# pc_healthypi_move_bottom_pcb_v3.net
KiCad netlist of a schematic drawn in EAGLE
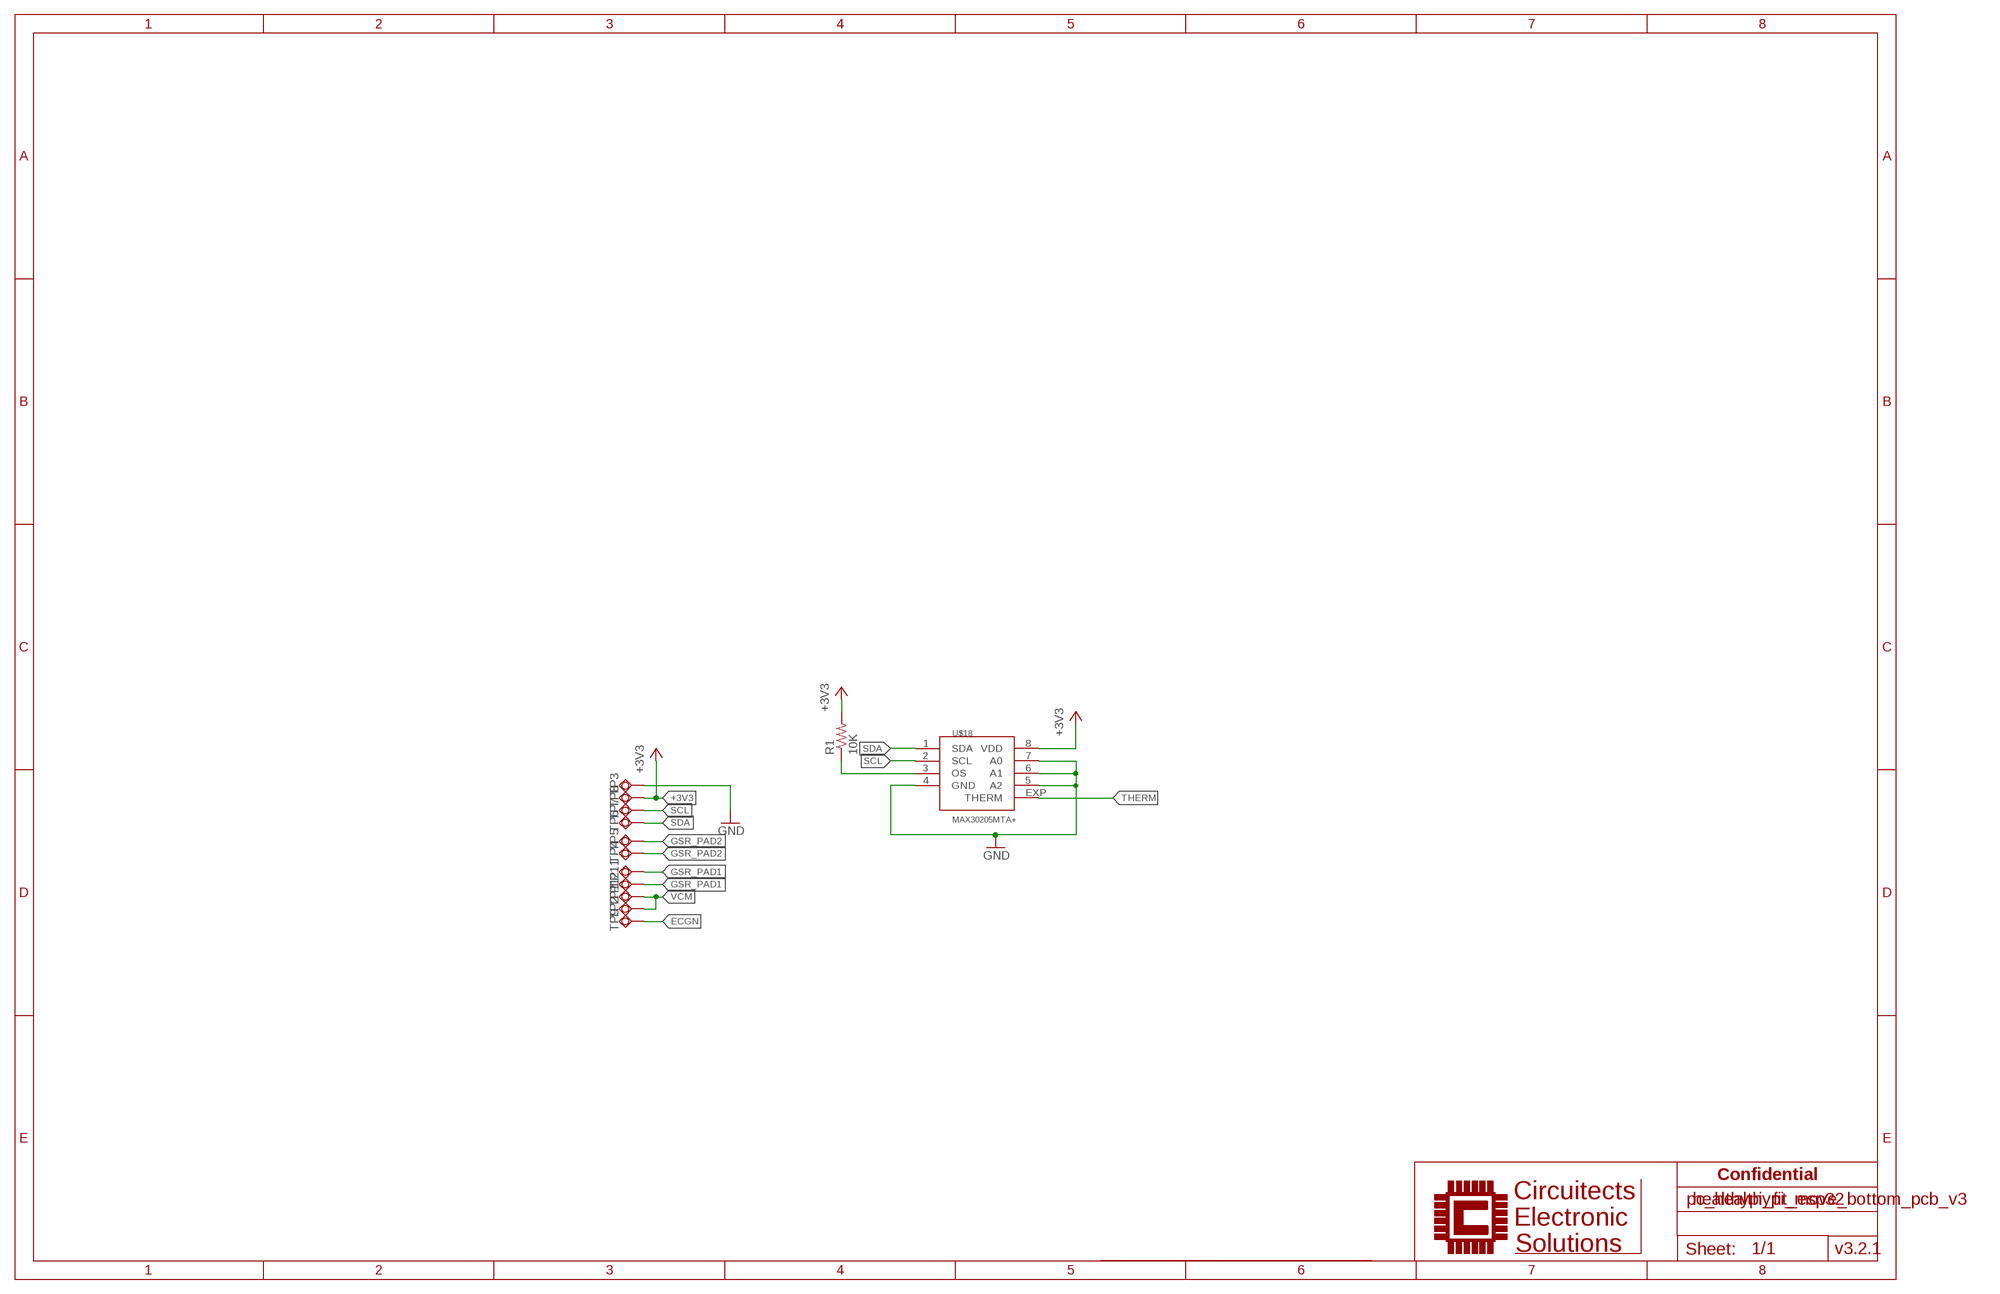
[diagram p0: schematic, sheet 1]

(export (version "E")
  (design (tool "Eeschema 10.0.6"))
  (components
    (comp (ref "R1")
      (value "10K")
      (footprint "eagle-import:R0201")
      (libsource (lib "eagle-import") (part "R-US_R0201"))
    )
    (comp (ref "TP1")
      (value "TPSQTP20SQ")
      (footprint "eagle-import:TP20SQ")
      (libsource (lib "eagle-import") (part "TPSQTP20SQ"))
    )
    (comp (ref "TP2")
      (value "TPSQTP20SQ")
      (footprint "eagle-import:TP20SQ")
      (libsource (lib "eagle-import") (part "TPSQTP20SQ"))
    )
    (comp (ref "TP3")
      (value "TPSQTP20SQ")
      (footprint "eagle-import:TP20SQ")
      (libsource (lib "eagle-import") (part "TPSQTP20SQ"))
    )
    (comp (ref "TP4")
      (value "TPSQTP20SQ")
      (footprint "eagle-import:TP20SQ")
      (libsource (lib "eagle-import") (part "TPSQTP20SQ"))
    )
    (comp (ref "TP5")
      (value "TPSQTP20SQ")
      (footprint "eagle-import:TP20SQ")
      (libsource (lib "eagle-import") (part "TPSQTP20SQ"))
    )
    (comp (ref "TP6")
      (value "TPSQTP20SQ")
      (footprint "eagle-import:TP20SQ")
      (libsource (lib "eagle-import") (part "TPSQTP20SQ"))
    )
    (comp (ref "TP7")
      (value "TPSQTP20SQ")
      (footprint "eagle-import:TP20SQ")
      (libsource (lib "eagle-import") (part "TPSQTP20SQ"))
    )
    (comp (ref "TP8")
      (value "TPSQTP20SQ")
      (footprint "eagle-import:TP20SQ")
      (libsource (lib "eagle-import") (part "TPSQTP20SQ"))
    )
    (comp (ref "TP9")
      (value "TPSQTP20SQ")
      (footprint "eagle-import:TP20SQ")
      (libsource (lib "eagle-import") (part "TPSQTP20SQ"))
    )
    (comp (ref "TP11")
      (value "TPSQTP20SQ")
      (footprint "eagle-import:TP20SQ")
      (libsource (lib "eagle-import") (part "TPSQTP20SQ"))
    )
    (comp (ref "TP12")
      (value "TPSQTP20SQ")
      (footprint "eagle-import:TP20SQ")
      (libsource (lib "eagle-import") (part "TPSQTP20SQ"))
    )
    (comp (ref "U$18")
      (value "MAX30205MTA+")
      (footprint "eagle-import:TDFN-08")
      (libsource (lib "eagle-import") (part "MAX30205MTA+"))
    )
  )
  (nets
    (net (code "1") (name "+3V3") (class "Default")
      (node (ref "R1") (pin "2") (pinfunction "2_2") (pintype "passive"))
      (node (ref "TP8") (pin "TP") (pinfunction "TP_TP") (pintype "input"))
      (node (ref "U$18") (pin "8") (pinfunction "VDD_8") (pintype "bidirectional"))
    )
    (net (code "2") (name "ECGN") (class "Default")
      (node (ref "TP9") (pin "TP") (pinfunction "TP_TP") (pintype "input"))
    )
    (net (code "3") (name "GND") (class "Default")
      (node (ref "TP3") (pin "TP") (pinfunction "TP_TP") (pintype "input"))
      (node (ref "U$18") (pin "4") (pinfunction "GND_4") (pintype "bidirectional"))
      (node (ref "U$18") (pin "5") (pinfunction "A2_5") (pintype "bidirectional"))
      (node (ref "U$18") (pin "6") (pinfunction "A1_6") (pintype "bidirectional"))
      (node (ref "U$18") (pin "7") (pinfunction "A0_7") (pintype "bidirectional"))
    )
    (net (code "4") (name "GSR_PAD1") (class "Default")
      (node (ref "TP11") (pin "TP") (pinfunction "TP_TP") (pintype "input"))
      (node (ref "TP12") (pin "TP") (pinfunction "TP_TP") (pintype "input"))
    )
    (net (code "5") (name "GSR_PAD2") (class "Default")
      (node (ref "TP4") (pin "TP") (pinfunction "TP_TP") (pintype "input"))
      (node (ref "TP5") (pin "TP") (pinfunction "TP_TP") (pintype "input"))
    )
    (net (code "6") (name "Net-(U$18-OS)") (class "Default")
      (node (ref "R1") (pin "1") (pinfunction "1_1") (pintype "passive"))
      (node (ref "U$18") (pin "3") (pinfunction "OS_3") (pintype "bidirectional"))
    )
    (net (code "7") (name "SCL") (class "Default")
      (node (ref "TP7") (pin "TP") (pinfunction "TP_TP") (pintype "input"))
      (node (ref "U$18") (pin "2") (pinfunction "SCL_2") (pintype "bidirectional"))
    )
    (net (code "8") (name "SDA") (class "Default")
      (node (ref "TP6") (pin "TP") (pinfunction "TP_TP") (pintype "input"))
      (node (ref "U$18") (pin "1") (pinfunction "SDA_1") (pintype "bidirectional"))
    )
    (net (code "9") (name "THERM") (class "Default")
      (node (ref "U$18") (pin "EXP") (pinfunction "THERM_EXP") (pintype "bidirectional"))
    )
    (net (code "10") (name "VCM") (class "Default")
      (node (ref "TP1") (pin "TP") (pinfunction "TP_TP") (pintype "input"))
      (node (ref "TP2") (pin "TP") (pinfunction "TP_TP") (pintype "input"))
    )
  )
)
